# SH-SwitchNode-CT1.net
KiCad netlist of a schematic drawn in EAGLE
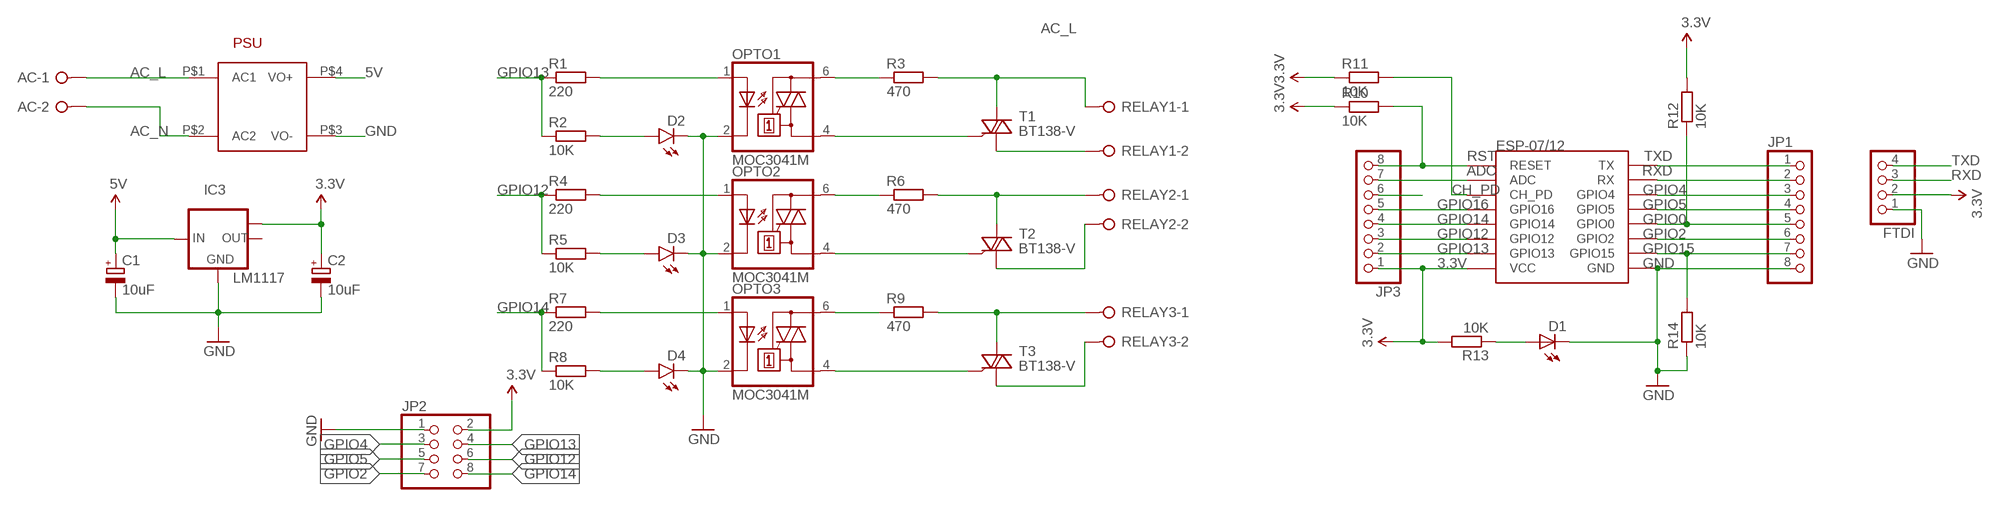
[diagram p0: schematic, sheet 1]

(export (version "E")
  (design (tool "Eeschema 10.0.6"))
  (components
    (comp (ref "AC")
      (value "W237-02P")
      (footprint "eagle-import:W237-132")
      (libsource (lib "eagle-import") (part "W237-02P"))
    )
    (comp (ref "C1")
      (value "10uF")
      (footprint "eagle-import:B_3528-21W")
      (libsource (lib "eagle-import") (part "CPOL-EUB/3528-21W"))
    )
    (comp (ref "C2")
      (value "10uF")
      (footprint "eagle-import:B_3528-21W")
      (libsource (lib "eagle-import") (part "CPOL-EUB/3528-21W"))
    )
    (comp (ref "D1")
      (value "LEDCHIPLED_0805")
      (footprint "eagle-import:CHIPLED_0805")
      (libsource (lib "eagle-import") (part "LEDCHIPLED_0805"))
    )
    (comp (ref "D2")
      (value "LED3MM")
      (footprint "eagle-import:LED3MM")
      (libsource (lib "eagle-import") (part "LED3MM"))
    )
    (comp (ref "D3")
      (value "LED3MM")
      (footprint "eagle-import:LED3MM")
      (libsource (lib "eagle-import") (part "LED3MM"))
    )
    (comp (ref "D4")
      (value "LED3MM")
      (footprint "eagle-import:LED3MM")
      (libsource (lib "eagle-import") (part "LED3MM"))
    )
    (comp (ref "ESP-07/12")
      (value "ESP12SMD")
      (footprint "eagle-import:ESP12-SMD")
      (libsource (lib "eagle-import") (part "ESP12SMD"))
    )
    (comp (ref "FTDI")
      (value "PINHD-1X4")
      (footprint "eagle-import:1X04")
      (libsource (lib "eagle-import") (part "PINHD-1X4"))
    )
    (comp (ref "IC3")
      (value "LM1117")
      (footprint "eagle-import:SOT223")
      (libsource (lib "eagle-import") (part "LM1117MPX-3.3"))
    )
    (comp (ref "JP1")
      (value "PINHD-1X8")
      (footprint "eagle-import:1X08")
      (libsource (lib "eagle-import") (part "PINHD-1X8"))
    )
    (comp (ref "JP2")
      (value "PINHD-2X4")
      (footprint "eagle-import:2X04")
      (libsource (lib "eagle-import") (part "PINHD-2X4"))
    )
    (comp (ref "JP3")
      (value "PINHD-1X8")
      (footprint "eagle-import:1X08")
      (libsource (lib "eagle-import") (part "PINHD-1X8"))
    )
    (comp (ref "OPTO1")
      (value "MOC3041M")
      (footprint "eagle-import:DIL06")
      (fields (field (name "MF") "FAIRCHILD SEMICONDUCTOR"))
      (libsource (lib "eagle-import") (part "MOC3041M"))
    )
    (comp (ref "OPTO2")
      (value "MOC3041M")
      (footprint "eagle-import:DIL06")
      (fields (field (name "MF") "FAIRCHILD SEMICONDUCTOR"))
      (libsource (lib "eagle-import") (part "MOC3041M"))
    )
    (comp (ref "OPTO3")
      (value "MOC3041M")
      (footprint "eagle-import:DIL06")
      (fields (field (name "MF") "FAIRCHILD SEMICONDUCTOR"))
      (libsource (lib "eagle-import") (part "MOC3041M"))
    )
    (comp (ref "PSU")
      (value "HLK-PM01")
      (footprint "eagle-import:HLK-PM01")
      (libsource (lib "eagle-import") (part "HLK-PM01"))
    )
    (comp (ref "R1")
      (value "220")
      (footprint "eagle-import:R0805")
      (libsource (lib "eagle-import") (part "R-EU_R0805"))
    )
    (comp (ref "R2")
      (value "10K")
      (footprint "eagle-import:R0805")
      (libsource (lib "eagle-import") (part "R-EU_R0805"))
    )
    (comp (ref "R3")
      (value "470")
      (footprint "eagle-import:R0805")
      (libsource (lib "eagle-import") (part "R-EU_R0805"))
    )
    (comp (ref "R4")
      (value "220")
      (footprint "eagle-import:R0805")
      (libsource (lib "eagle-import") (part "R-EU_R0805"))
    )
    (comp (ref "R5")
      (value "10K")
      (footprint "eagle-import:R0805")
      (libsource (lib "eagle-import") (part "R-EU_R0805"))
    )
    (comp (ref "R6")
      (value "470")
      (footprint "eagle-import:R0805")
      (libsource (lib "eagle-import") (part "R-EU_R0805"))
    )
    (comp (ref "R7")
      (value "220")
      (footprint "eagle-import:R0805")
      (libsource (lib "eagle-import") (part "R-EU_R0805"))
    )
    (comp (ref "R8")
      (value "10K")
      (footprint "eagle-import:R0805")
      (libsource (lib "eagle-import") (part "R-EU_R0805"))
    )
    (comp (ref "R9")
      (value "470")
      (footprint "eagle-import:R0805")
      (libsource (lib "eagle-import") (part "R-EU_R0805"))
    )
    (comp (ref "R10")
      (value "10K")
      (footprint "eagle-import:R0805")
      (libsource (lib "eagle-import") (part "R-EU_R0805"))
    )
    (comp (ref "R11")
      (value "10K")
      (footprint "eagle-import:R0805")
      (libsource (lib "eagle-import") (part "R-EU_R0805"))
    )
    (comp (ref "R12")
      (value "10K")
      (footprint "eagle-import:R0805")
      (libsource (lib "eagle-import") (part "R-EU_R0805"))
    )
    (comp (ref "R13")
      (value "10K")
      (footprint "eagle-import:R0805")
      (libsource (lib "eagle-import") (part "R-EU_R0805"))
    )
    (comp (ref "R14")
      (value "10K")
      (footprint "eagle-import:R0805")
      (libsource (lib "eagle-import") (part "R-EU_R0805"))
    )
    (comp (ref "RELAY1")
      (value "W237-02P")
      (footprint "eagle-import:W237-132")
      (libsource (lib "eagle-import") (part "W237-02P"))
    )
    (comp (ref "RELAY2")
      (value "W237-02P")
      (footprint "eagle-import:W237-132")
      (libsource (lib "eagle-import") (part "W237-02P"))
    )
    (comp (ref "RELAY3")
      (value "W237-02P")
      (footprint "eagle-import:W237-132")
      (libsource (lib "eagle-import") (part "W237-02P"))
    )
    (comp (ref "T1")
      (value "BT138-V")
      (footprint "eagle-import:TO220BV")
      (libsource (lib "eagle-import") (part "BT138-V"))
    )
    (comp (ref "T2")
      (value "BT138-V")
      (footprint "eagle-import:TO220BV")
      (libsource (lib "eagle-import") (part "BT138-V"))
    )
    (comp (ref "T3")
      (value "BT138-V")
      (footprint "eagle-import:TO220BV")
      (libsource (lib "eagle-import") (part "BT138-V"))
    )
  )
  (nets
    (net (code "1") (name "/AC_L") (class "Default")
      (node (ref "AC") (pin "1") (pinfunction "KL_1") (pintype "passive"))
      (node (ref "PSU") (pin "P$1") (pinfunction "AC1_P$1") (pintype "input"))
      (node (ref "R3") (pin "2") (pinfunction "2_2") (pintype "passive"))
      (node (ref "R6") (pin "2") (pinfunction "2_2") (pintype "passive"))
      (node (ref "R9") (pin "2") (pinfunction "2_2") (pintype "passive"))
      (node (ref "RELAY1") (pin "1") (pinfunction "KL_1") (pintype "passive"))
      (node (ref "RELAY2") (pin "1") (pinfunction "KL_1") (pintype "passive"))
      (node (ref "RELAY3") (pin "1") (pinfunction "KL_1") (pintype "passive"))
      (node (ref "T1") (pin "T2") (pinfunction "A2_T2") (pintype "passive"))
      (node (ref "T2") (pin "T2") (pinfunction "A2_T2") (pintype "passive"))
      (node (ref "T3") (pin "T2") (pinfunction "A2_T2") (pintype "passive"))
    )
    (net (code "2") (name "/AC_N") (class "Default")
      (node (ref "AC") (pin "2") (pinfunction "KL_2") (pintype "passive"))
      (node (ref "PSU") (pin "P$2") (pinfunction "AC2_P$2") (pintype "input"))
    )
    (net (code "3") (name "/ADC") (class "Default")
      (node (ref "ESP-07/12") (pin "ADC") (pinfunction "ADC_ADC") (pintype "bidirectional"))
      (node (ref "JP3") (pin "7") (pinfunction "7_7") (pintype "passive"))
    )
    (net (code "4") (name "/CH_PD") (class "Default")
      (node (ref "ESP-07/12") (pin "CH_PD") (pinfunction "CH_PD_CH_PD") (pintype "bidirectional"))
      (node (ref "JP3") (pin "6") (pinfunction "6_6") (pintype "passive"))
      (node (ref "R11") (pin "2") (pinfunction "2_2") (pintype "passive"))
    )
    (net (code "5") (name "/GPIO0") (class "Default")
      (node (ref "ESP-07/12") (pin "GPIO0") (pinfunction "GPIO0_GPIO0") (pintype "bidirectional"))
      (node (ref "JP1") (pin "5") (pinfunction "5_5") (pintype "passive"))
      (node (ref "R12") (pin "1") (pinfunction "1_1") (pintype "passive"))
    )
    (net (code "6") (name "/GPIO15") (class "Default")
      (node (ref "ESP-07/12") (pin "GPIO15") (pinfunction "GPIO15_GPIO15") (pintype "bidirectional"))
      (node (ref "JP1") (pin "7") (pinfunction "7_7") (pintype "passive"))
      (node (ref "R14") (pin "2") (pinfunction "2_2") (pintype "passive"))
    )
    (net (code "7") (name "/GPIO16") (class "Default")
      (node (ref "ESP-07/12") (pin "GPIO16") (pinfunction "GPIO16_GPIO16") (pintype "bidirectional"))
      (node (ref "JP3") (pin "5") (pinfunction "5_5") (pintype "passive"))
    )
    (net (code "8") (name "/RST") (class "Default")
      (node (ref "ESP-07/12") (pin "RESET") (pinfunction "RESET_RESET") (pintype "bidirectional"))
      (node (ref "JP3") (pin "8") (pinfunction "8_8") (pintype "passive"))
      (node (ref "R10") (pin "2") (pinfunction "2_2") (pintype "passive"))
    )
    (net (code "9") (name "/RXD") (class "Default")
      (node (ref "ESP-07/12") (pin "RXD0") (pinfunction "RX_RXD0") (pintype "bidirectional"))
      (node (ref "FTDI") (pin "3") (pinfunction "3_3") (pintype "passive"))
      (node (ref "JP1") (pin "2") (pinfunction "2_2") (pintype "passive"))
    )
    (net (code "10") (name "/TXD") (class "Default")
      (node (ref "ESP-07/12") (pin "TXD0") (pinfunction "TX_TXD0") (pintype "bidirectional"))
      (node (ref "FTDI") (pin "4") (pinfunction "4_4") (pintype "passive"))
      (node (ref "JP1") (pin "1") (pinfunction "1_1") (pintype "passive"))
    )
    (net (code "11") (name "3.3V") (class "Default")
      (node (ref "C2") (pin "+") (pinfunction "+_+") (pintype "passive"))
      (node (ref "ESP-07/12") (pin "VCC") (pinfunction "VCC_VCC") (pintype "bidirectional"))
      (node (ref "FTDI") (pin "2") (pinfunction "2_2") (pintype "passive"))
      (node (ref "IC3") (pin "TAB") (pinfunction "OUT1_TAB") (pintype "passive"))
      (node (ref "JP2") (pin "2") (pinfunction "2_2") (pintype "passive"))
      (node (ref "JP3") (pin "1") (pinfunction "1_1") (pintype "passive"))
      (node (ref "R10") (pin "1") (pinfunction "1_1") (pintype "passive"))
      (node (ref "R11") (pin "1") (pinfunction "1_1") (pintype "passive"))
      (node (ref "R12") (pin "2") (pinfunction "2_2") (pintype "passive"))
      (node (ref "R13") (pin "2") (pinfunction "2_2") (pintype "passive"))
    )
    (net (code "12") (name "5V") (class "Default")
      (node (ref "C1") (pin "+") (pinfunction "+_+") (pintype "passive"))
      (node (ref "IC3") (pin "3") (pinfunction "IN_3") (pintype "input"))
      (node (ref "PSU") (pin "P$4") (pinfunction "VO+_P$4") (pintype "power_in"))
    )
    (net (code "13") (name "GND") (class "Default")
      (node (ref "C1") (pin "-") (pinfunction "-_-") (pintype "passive"))
      (node (ref "C2") (pin "-") (pinfunction "-_-") (pintype "passive"))
      (node (ref "D1") (pin "C") (pinfunction "C_C") (pintype "passive"))
      (node (ref "D2") (pin "K") (pinfunction "C_K") (pintype "passive"))
      (node (ref "D3") (pin "K") (pinfunction "C_K") (pintype "passive"))
      (node (ref "D4") (pin "K") (pinfunction "C_K") (pintype "passive"))
      (node (ref "ESP-07/12") (pin "GND") (pinfunction "GND_GND") (pintype "bidirectional"))
      (node (ref "FTDI") (pin "1") (pinfunction "1_1") (pintype "passive"))
      (node (ref "IC3") (pin "1") (pinfunction "GND_1") (pintype "input"))
      (node (ref "JP1") (pin "8") (pinfunction "8_8") (pintype "passive"))
      (node (ref "JP2") (pin "1") (pinfunction "1_1") (pintype "passive"))
      (node (ref "OPTO1") (pin "2") (pinfunction "C_2") (pintype "passive"))
      (node (ref "OPTO2") (pin "2") (pinfunction "C_2") (pintype "passive"))
      (node (ref "OPTO3") (pin "2") (pinfunction "C_2") (pintype "passive"))
      (node (ref "PSU") (pin "P$3") (pinfunction "VO-_P$3") (pintype "power_in"))
      (node (ref "R14") (pin "1") (pinfunction "1_1") (pintype "passive"))
    )
    (net (code "14") (name "GPIO2") (class "Default")
      (node (ref "ESP-07/12") (pin "GPIO2") (pinfunction "GPIO2_GPIO2") (pintype "bidirectional"))
      (node (ref "JP1") (pin "6") (pinfunction "6_6") (pintype "passive"))
      (node (ref "JP2") (pin "7") (pinfunction "7_7") (pintype "passive"))
    )
    (net (code "15") (name "GPIO4") (class "Default")
      (node (ref "ESP-07/12") (pin "GPIO4") (pinfunction "GPIO4_GPIO4") (pintype "bidirectional"))
      (node (ref "JP1") (pin "3") (pinfunction "3_3") (pintype "passive"))
      (node (ref "JP2") (pin "3") (pinfunction "3_3") (pintype "passive"))
    )
    (net (code "16") (name "GPIO5") (class "Default")
      (node (ref "ESP-07/12") (pin "GPIO5") (pinfunction "GPIO5_GPIO5") (pintype "bidirectional"))
      (node (ref "JP1") (pin "4") (pinfunction "4_4") (pintype "passive"))
      (node (ref "JP2") (pin "5") (pinfunction "5_5") (pintype "passive"))
    )
    (net (code "17") (name "GPIO12") (class "Default")
      (node (ref "ESP-07/12") (pin "GPIO12") (pinfunction "GPIO12_GPIO12") (pintype "bidirectional"))
      (node (ref "JP2") (pin "6") (pinfunction "6_6") (pintype "passive"))
      (node (ref "JP3") (pin "3") (pinfunction "3_3") (pintype "passive"))
      (node (ref "R4") (pin "1") (pinfunction "1_1") (pintype "passive"))
      (node (ref "R5") (pin "1") (pinfunction "1_1") (pintype "passive"))
    )
    (net (code "18") (name "GPIO13") (class "Default")
      (node (ref "ESP-07/12") (pin "GPIO13") (pinfunction "GPIO13_GPIO13") (pintype "bidirectional"))
      (node (ref "JP2") (pin "4") (pinfunction "4_4") (pintype "passive"))
      (node (ref "JP3") (pin "2") (pinfunction "2_2") (pintype "passive"))
      (node (ref "R1") (pin "1") (pinfunction "1_1") (pintype "passive"))
      (node (ref "R2") (pin "1") (pinfunction "1_1") (pintype "passive"))
    )
    (net (code "19") (name "GPIO14") (class "Default")
      (node (ref "ESP-07/12") (pin "GPIO14") (pinfunction "GPIO14_GPIO14") (pintype "bidirectional"))
      (node (ref "JP2") (pin "8") (pinfunction "8_8") (pintype "passive"))
      (node (ref "JP3") (pin "4") (pinfunction "4_4") (pintype "passive"))
      (node (ref "R7") (pin "1") (pinfunction "1_1") (pintype "passive"))
      (node (ref "R8") (pin "1") (pinfunction "1_1") (pintype "passive"))
    )
    (net (code "20") (name "Net-(D1-PadA)") (class "Default")
      (node (ref "D1") (pin "A") (pinfunction "A_A") (pintype "passive"))
      (node (ref "R13") (pin "1") (pinfunction "1_1") (pintype "passive"))
    )
    (net (code "21") (name "Net-(D2-PadA)") (class "Default")
      (node (ref "D2") (pin "A") (pinfunction "A_A") (pintype "passive"))
      (node (ref "R2") (pin "2") (pinfunction "2_2") (pintype "passive"))
    )
    (net (code "22") (name "Net-(D3-PadA)") (class "Default")
      (node (ref "D3") (pin "A") (pinfunction "A_A") (pintype "passive"))
      (node (ref "R5") (pin "2") (pinfunction "2_2") (pintype "passive"))
    )
    (net (code "23") (name "Net-(D4-PadA)") (class "Default")
      (node (ref "D4") (pin "A") (pinfunction "A_A") (pintype "passive"))
      (node (ref "R8") (pin "2") (pinfunction "2_2") (pintype "passive"))
    )
    (net (code "24") (name "Net-(OPTO1-A)") (class "Default")
      (node (ref "OPTO1") (pin "1") (pinfunction "A_1") (pintype "passive"))
      (node (ref "R1") (pin "2") (pinfunction "2_2") (pintype "passive"))
    )
    (net (code "25") (name "Net-(OPTO1-A1)") (class "Default")
      (node (ref "OPTO1") (pin "4") (pinfunction "A1_4") (pintype "passive"))
      (node (ref "T1") (pin "G") (pinfunction "G_G") (pintype "passive"))
    )
    (net (code "26") (name "Net-(OPTO1-A2)") (class "Default")
      (node (ref "OPTO1") (pin "6") (pinfunction "A2_6") (pintype "passive"))
      (node (ref "R3") (pin "1") (pinfunction "1_1") (pintype "passive"))
    )
    (net (code "27") (name "Net-(OPTO2-A)") (class "Default")
      (node (ref "OPTO2") (pin "1") (pinfunction "A_1") (pintype "passive"))
      (node (ref "R4") (pin "2") (pinfunction "2_2") (pintype "passive"))
    )
    (net (code "28") (name "Net-(OPTO2-A1)") (class "Default")
      (node (ref "OPTO2") (pin "4") (pinfunction "A1_4") (pintype "passive"))
      (node (ref "T2") (pin "G") (pinfunction "G_G") (pintype "passive"))
    )
    (net (code "29") (name "Net-(OPTO2-A2)") (class "Default")
      (node (ref "OPTO2") (pin "6") (pinfunction "A2_6") (pintype "passive"))
      (node (ref "R6") (pin "1") (pinfunction "1_1") (pintype "passive"))
    )
    (net (code "30") (name "Net-(OPTO3-A)") (class "Default")
      (node (ref "OPTO3") (pin "1") (pinfunction "A_1") (pintype "passive"))
      (node (ref "R7") (pin "2") (pinfunction "2_2") (pintype "passive"))
    )
    (net (code "31") (name "Net-(OPTO3-A1)") (class "Default")
      (node (ref "OPTO3") (pin "4") (pinfunction "A1_4") (pintype "passive"))
      (node (ref "T3") (pin "G") (pinfunction "G_G") (pintype "passive"))
    )
    (net (code "32") (name "Net-(OPTO3-A2)") (class "Default")
      (node (ref "OPTO3") (pin "6") (pinfunction "A2_6") (pintype "passive"))
      (node (ref "R9") (pin "1") (pinfunction "1_1") (pintype "passive"))
    )
    (net (code "33") (name "Net-(RELAY1B-KL)") (class "Default")
      (node (ref "RELAY1") (pin "2") (pinfunction "KL_2") (pintype "passive"))
      (node (ref "T1") (pin "T1") (pinfunction "A1_T1") (pintype "passive"))
    )
    (net (code "34") (name "Net-(RELAY2B-KL)") (class "Default")
      (node (ref "RELAY2") (pin "2") (pinfunction "KL_2") (pintype "passive"))
      (node (ref "T2") (pin "T1") (pinfunction "A1_T1") (pintype "passive"))
    )
    (net (code "35") (name "Net-(RELAY3B-KL)") (class "Default")
      (node (ref "RELAY3") (pin "2") (pinfunction "KL_2") (pintype "passive"))
      (node (ref "T3") (pin "T1") (pinfunction "A1_T1") (pintype "passive"))
    )
    (net (code "36") (name "unconnected-(IC3-OUT-Pad2)") (class "Default")
      (node (ref "IC3") (pin "2") (pinfunction "OUT_2") (pintype "passive"))
    )
  )
)
